# DFN-4_1_6x1_2_EP_Breakout.net
KiCad netlist of a schematic drawn in EAGLE
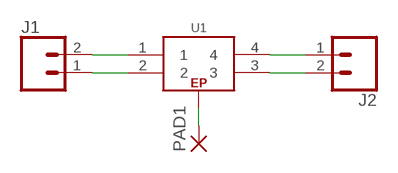
[diagram p0: schematic, sheet 1]

(export (version "E")
  (design (tool "Eeschema 10.0.6"))
  (components
    (comp (ref "J1")
      (value "CONN_02")
      (footprint "eagle-import:1X02")
      (libsource (lib "eagle-import") (part "CONN_02"))
    )
    (comp (ref "J2")
      (value "CONN_02")
      (footprint "eagle-import:1X02")
      (libsource (lib "eagle-import") (part "CONN_02"))
    )
    (comp (ref "PAD1")
      (value "SMD2")
      (footprint "eagle-import:SMD1,27-2,54")
      (fields (field (name "MPN") "DNP"))
      (libsource (lib "eagle-import") (part "SMD2"))
    )
    (comp (ref "U1")
      (value "GEN_4_EPTDFN_4")
      (footprint "eagle-import:TDFN_4")
      (libsource (lib "eagle-import") (part "GEN_4_EPTDFN_4"))
    )
  )
  (nets
    (net (code "1") (name "Net-(J1-Pad1)") (class "Default")
      (node (ref "J1") (pin "1") (pinfunction "1_1") (pintype "passive"))
      (node (ref "U1") (pin "2") (pinfunction "2_2") (pintype "bidirectional"))
    )
    (net (code "2") (name "Net-(J1-Pad2)") (class "Default")
      (node (ref "J1") (pin "2") (pinfunction "2_2") (pintype "passive"))
      (node (ref "U1") (pin "1") (pinfunction "1_1") (pintype "bidirectional"))
    )
    (net (code "3") (name "Net-(J2-Pad1)") (class "Default")
      (node (ref "J2") (pin "1") (pinfunction "1_1") (pintype "passive"))
      (node (ref "U1") (pin "4") (pinfunction "4_4") (pintype "bidirectional"))
    )
    (net (code "4") (name "Net-(J2-Pad2)") (class "Default")
      (node (ref "J2") (pin "2") (pinfunction "2_2") (pintype "passive"))
      (node (ref "U1") (pin "3") (pinfunction "3_3") (pintype "bidirectional"))
    )
    (net (code "5") (name "Net-(PAD1-P)") (class "Default")
      (node (ref "PAD1") (pin "1") (pinfunction "P_1") (pintype "passive"))
      (node (ref "U1") (pin "EP") (pinfunction "EP_EP") (pintype "passive"))
    )
  )
)
